# tec_controller.net
KiCad netlist of a schematic drawn in EAGLE
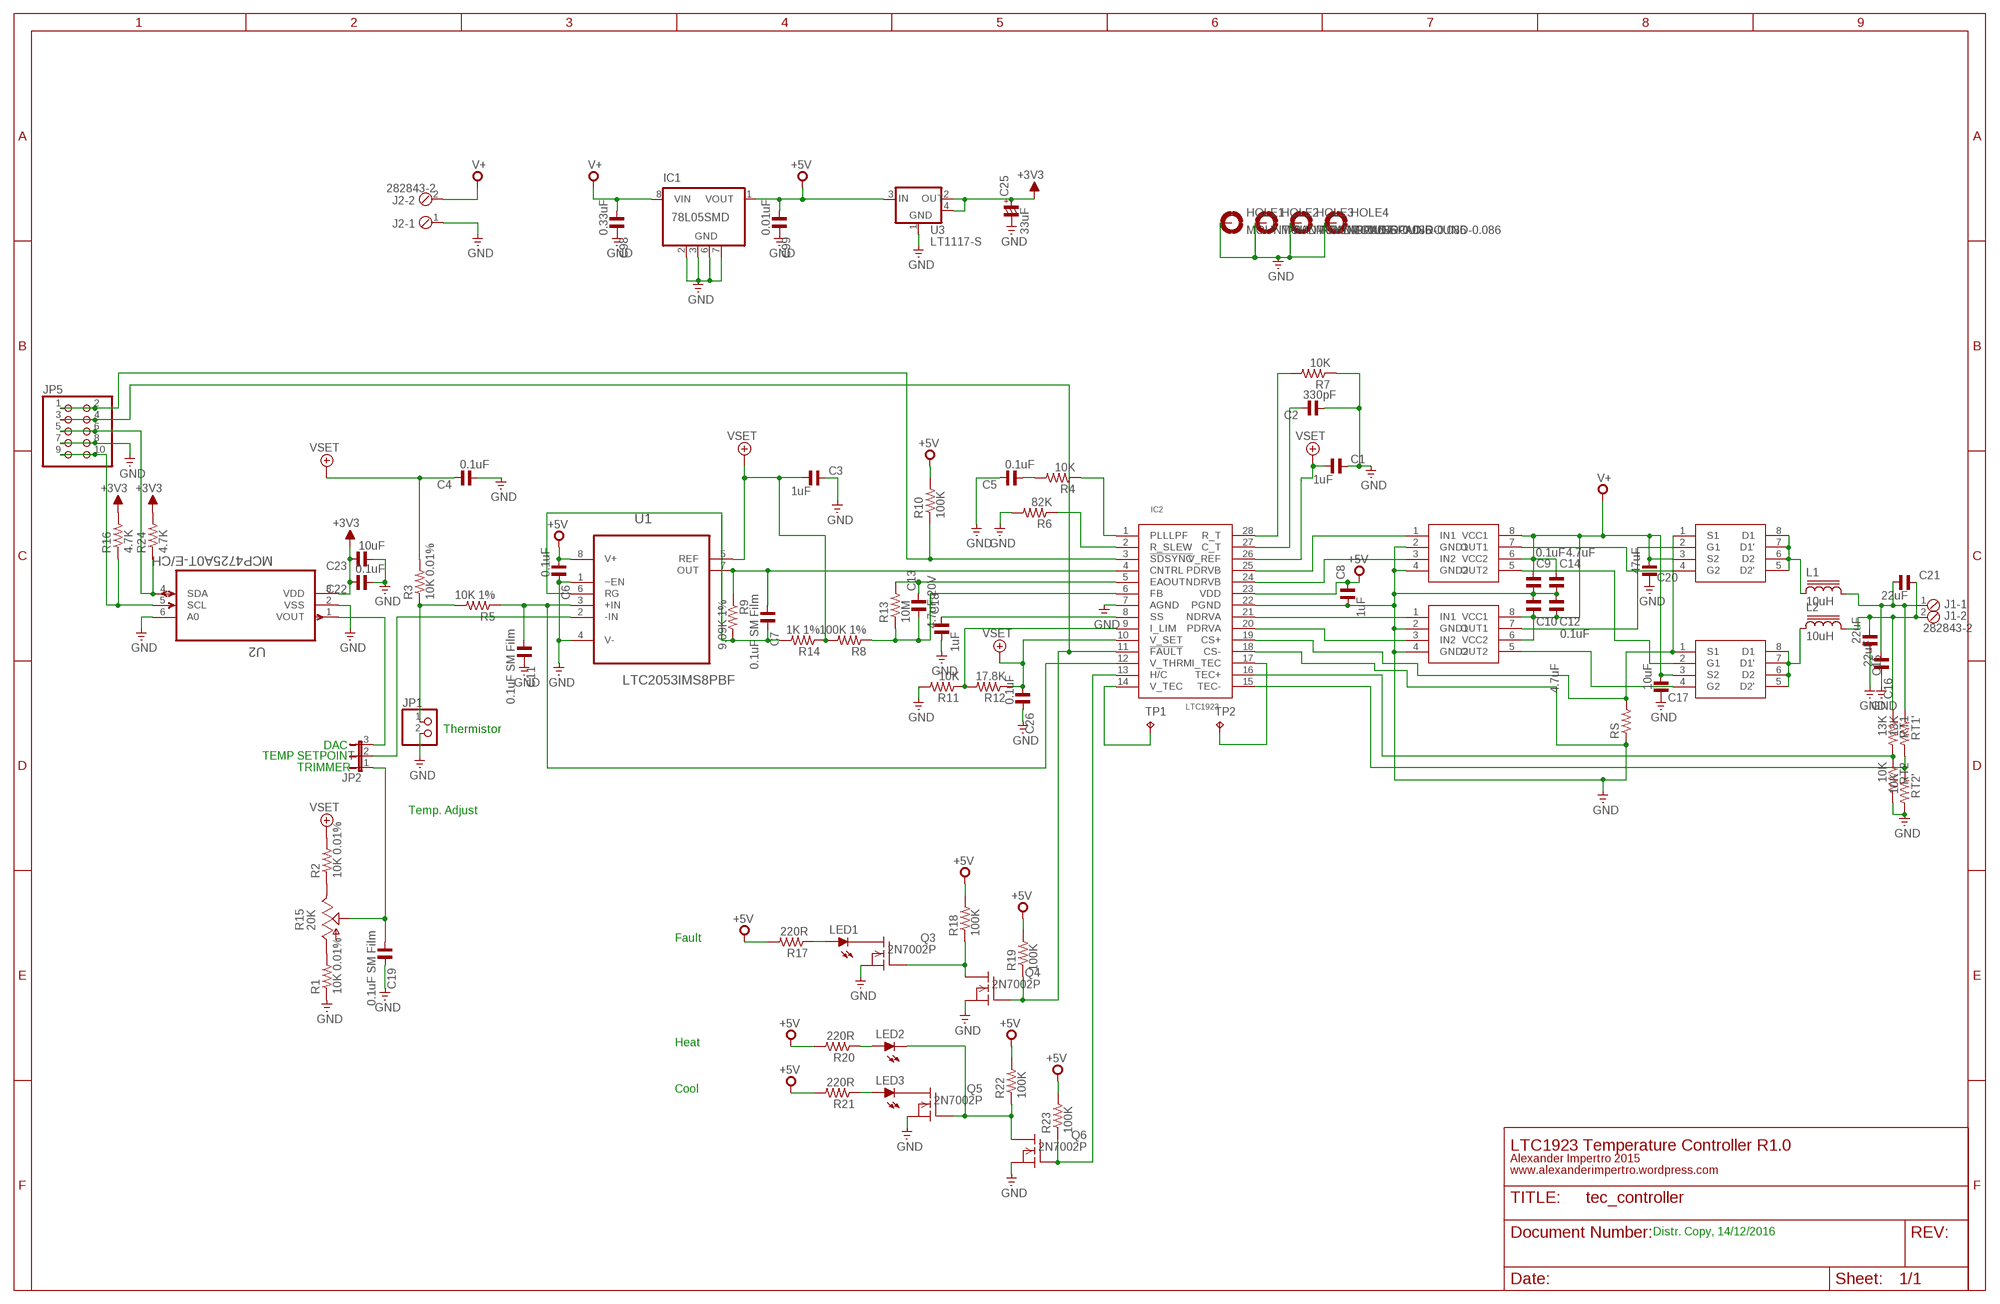
[diagram p0: schematic, sheet 1]

(export (version "E")
  (design (tool "Eeschema 10.0.6"))
  (components
    (comp (ref "C1")
      (value "1uF")
      (footprint "eagle-import:C0603")
      (libsource (lib "eagle-import") (part "C-EUC0603"))
    )
    (comp (ref "C2")
      (value "330pF")
      (footprint "eagle-import:C0603")
      (libsource (lib "eagle-import") (part "C-EUC0603"))
    )
    (comp (ref "C3")
      (value "1uF")
      (footprint "eagle-import:C0603")
      (libsource (lib "eagle-import") (part "C-EUC0603"))
    )
    (comp (ref "C4")
      (value "0.1uF")
      (footprint "eagle-import:C0603")
      (libsource (lib "eagle-import") (part "C-EUC0603"))
    )
    (comp (ref "C5")
      (value "0.1uF")
      (footprint "eagle-import:C0603")
      (libsource (lib "eagle-import") (part "C-EUC0603"))
    )
    (comp (ref "C6")
      (value "0.1uF")
      (footprint "eagle-import:C0603")
      (libsource (lib "eagle-import") (part "C-EUC0603"))
    )
    (comp (ref "C7")
      (value "0.1uF SM Film")
      (footprint "eagle-import:C0805")
      (libsource (lib "eagle-import") (part "C-EUC0805"))
    )
    (comp (ref "C8")
      (value "1uF")
      (footprint "eagle-import:C0603")
      (libsource (lib "eagle-import") (part "C-EUC0603"))
    )
    (comp (ref "C9")
      (value "0.1uF")
      (footprint "eagle-import:C0603")
      (libsource (lib "eagle-import") (part "C-EUC0603"))
    )
    (comp (ref "C10")
      (value "4.7uF")
      (footprint "eagle-import:C0603")
      (libsource (lib "eagle-import") (part "C-EUC0603"))
    )
    (comp (ref "C11")
      (value "0.1uF SM Film")
      (footprint "eagle-import:C0805")
      (libsource (lib "eagle-import") (part "C-EUC0805"))
    )
    (comp (ref "C12")
      (value "0.1uF")
      (footprint "eagle-import:C0603")
      (libsource (lib "eagle-import") (part "C-EUC0603"))
    )
    (comp (ref "C13")
      (value "4.7uF 20V")
      (footprint "eagle-import:C1206")
      (libsource (lib "eagle-import") (part "C-EUC1206"))
    )
    (comp (ref "C14")
      (value "4.7uF")
      (footprint "eagle-import:C0603")
      (libsource (lib "eagle-import") (part "C-EUC0603"))
    )
    (comp (ref "C15")
      (value "22uF")
      (footprint "eagle-import:C0603")
      (libsource (lib "eagle-import") (part "C-EUC0603"))
    )
    (comp (ref "C16")
      (value "22uF")
      (footprint "eagle-import:C0603")
      (libsource (lib "eagle-import") (part "C-EUC0603"))
    )
    (comp (ref "C17")
      (value "10uF")
      (footprint "eagle-import:C0603")
      (libsource (lib "eagle-import") (part "C-EUC0603"))
    )
    (comp (ref "C18")
      (value "1uF")
      (footprint "eagle-import:C0603")
      (libsource (lib "eagle-import") (part "C-EUC0603"))
    )
    (comp (ref "C19")
      (value "0.1uF SM Film")
      (footprint "eagle-import:C0805")
      (libsource (lib "eagle-import") (part "C-EUC0805"))
    )
    (comp (ref "C20")
      (value "47uF")
      (footprint "eagle-import:C0805")
      (libsource (lib "eagle-import") (part "C-EUC0805"))
    )
    (comp (ref "C21")
      (value "22uF")
      (footprint "eagle-import:C0603")
      (libsource (lib "eagle-import") (part "C-EUC0603"))
    )
    (comp (ref "C22")
      (value "0.1uF")
      (footprint "eagle-import:C0603")
      (libsource (lib "eagle-import") (part "C-EUC0603"))
    )
    (comp (ref "C23")
      (value "10uF")
      (footprint "eagle-import:C0603")
      (libsource (lib "eagle-import") (part "C-EUC0603"))
    )
    (comp (ref "C25")
      (value "33uF")
      (footprint "eagle-import:153CLV-0505")
      (libsource (lib "eagle-import") (part "CPOL-EU153CLV-0505"))
    )
    (comp (ref "C26")
      (value "0.1uF")
      (footprint "eagle-import:C0603")
      (libsource (lib "eagle-import") (part "C-EUC0603"))
    )
    (comp (ref "C98")
      (value "0.33uF")
      (footprint "eagle-import:C0805")
      (libsource (lib "eagle-import") (part "C-EUC0805"))
    )
    (comp (ref "C99")
      (value "0.01uF")
      (footprint "eagle-import:C0805")
      (libsource (lib "eagle-import") (part "C-EUC0805"))
    )
    (comp (ref "HOLE1")
      (value "MOUNT-PAD-ROUND-0.086")
      (footprint "eagle-import:086-PAD")
      (libsource (lib "eagle-import") (part "MOUNT-PAD-ROUND-0.086"))
    )
    (comp (ref "HOLE2")
      (value "MOUNT-PAD-ROUND-0.086")
      (footprint "eagle-import:086-PAD")
      (libsource (lib "eagle-import") (part "MOUNT-PAD-ROUND-0.086"))
    )
    (comp (ref "HOLE3")
      (value "MOUNT-PAD-ROUND-0.086")
      (footprint "eagle-import:086-PAD")
      (libsource (lib "eagle-import") (part "MOUNT-PAD-ROUND-0.086"))
    )
    (comp (ref "HOLE4")
      (value "MOUNT-PAD-ROUND-0.086")
      (footprint "eagle-import:086-PAD")
      (libsource (lib "eagle-import") (part "MOUNT-PAD-ROUND-0.086"))
    )
    (comp (ref "IC1")
      (value "78L05SMD")
      (footprint "eagle-import:SO08")
      (libsource (lib "eagle-import") (part "78LSMD05"))
    )
    (comp (ref "IC2")
      (value "LTC1923")
      (footprint "eagle-import:SSOP28")
      (libsource (lib "eagle-import") (part "LTC1923"))
    )
    (comp (ref "IC3")
      (value "LTC1693-1")
      (footprint "eagle-import:SO-08")
      (libsource (lib "eagle-import") (part "LTC1693-1"))
    )
    (comp (ref "IC4")
      (value "LTC1693-1")
      (footprint "eagle-import:SO-08")
      (libsource (lib "eagle-import") (part "LTC1693-1"))
    )
    (comp (ref "IC5")
      (value "IRF7343")
      (footprint "eagle-import:SO-08")
      (libsource (lib "eagle-import") (part "IRF7343"))
    )
    (comp (ref "IC6")
      (value "IRF7343")
      (footprint "eagle-import:SO-08")
      (libsource (lib "eagle-import") (part "IRF7343"))
    )
    (comp (ref "J1")
      (value "282843-2")
      (footprint "eagle-import:282843-2")
      (libsource (lib "eagle-import") (part "282843-2"))
    )
    (comp (ref "J2")
      (value "282843-2")
      (footprint "eagle-import:282843-2")
      (libsource (lib "eagle-import") (part "282843-2"))
    )
    (comp (ref "JP1")
      (value "PINHD-1X2")
      (footprint "eagle-import:1X02")
      (libsource (lib "eagle-import") (part "PINHD-1X2"))
    )
    (comp (ref "JP2")
      (value "JP2E")
      (footprint "eagle-import:JP2")
      (libsource (lib "eagle-import") (part "JP2E"))
    )
    (comp (ref "JP5")
      (value "PINHD-2X5")
      (footprint "eagle-import:2X05")
      (libsource (lib "eagle-import") (part "PINHD-2X5"))
    )
    (comp (ref "L1")
      (value "10uH")
      (footprint "eagle-import:DRA127")
      (libsource (lib "eagle-import") (part "DRA127"))
    )
    (comp (ref "L2")
      (value "10uH")
      (footprint "eagle-import:DRA127")
      (libsource (lib "eagle-import") (part "DRA127"))
    )
    (comp (ref "LED1")
      (value "LEDCHIPLED_0805")
      (footprint "eagle-import:CHIPLED_0805")
      (libsource (lib "eagle-import") (part "LEDCHIPLED_0805"))
    )
    (comp (ref "LED2")
      (value "LEDCHIPLED_0805")
      (footprint "eagle-import:CHIPLED_0805")
      (libsource (lib "eagle-import") (part "LEDCHIPLED_0805"))
    )
    (comp (ref "LED3")
      (value "LEDCHIPLED_0805")
      (footprint "eagle-import:CHIPLED_0805")
      (libsource (lib "eagle-import") (part "LEDCHIPLED_0805"))
    )
    (comp (ref "Q3")
      (value "2N7002P")
      (footprint "eagle-import:SOT95P230X110-3N")
      (libsource (lib "eagle-import") (part "2N7002P"))
    )
    (comp (ref "Q4")
      (value "2N7002P")
      (footprint "eagle-import:SOT95P230X110-3N")
      (libsource (lib "eagle-import") (part "2N7002P"))
    )
    (comp (ref "Q5")
      (value "2N7002P")
      (footprint "eagle-import:SOT95P230X110-3N")
      (libsource (lib "eagle-import") (part "2N7002P"))
    )
    (comp (ref "Q6")
      (value "2N7002P")
      (footprint "eagle-import:SOT95P230X110-3N")
      (libsource (lib "eagle-import") (part "2N7002P"))
    )
    (comp (ref "R1")
      (value "10K 0.01%")
      (footprint "eagle-import:R0603")
      (libsource (lib "eagle-import") (part "R-EU_R0603"))
    )
    (comp (ref "R2")
      (value "10K 0.01%")
      (footprint "eagle-import:R0603")
      (libsource (lib "eagle-import") (part "R-EU_R0603"))
    )
    (comp (ref "R3")
      (value "10K 0.01%")
      (footprint "eagle-import:R0603")
      (libsource (lib "eagle-import") (part "R-EU_R0603"))
    )
    (comp (ref "R4")
      (value "10K")
      (footprint "eagle-import:R0603")
      (libsource (lib "eagle-import") (part "R-EU_R0603"))
    )
    (comp (ref "R5")
      (value "10K 1%")
      (footprint "eagle-import:R0603")
      (libsource (lib "eagle-import") (part "R-EU_R0603"))
    )
    (comp (ref "R6")
      (value "82K")
      (footprint "eagle-import:R0603")
      (libsource (lib "eagle-import") (part "R-EU_R0603"))
    )
    (comp (ref "R7")
      (value "10K")
      (footprint "eagle-import:R0603")
      (libsource (lib "eagle-import") (part "R-EU_R0603"))
    )
    (comp (ref "R8")
      (value "100K 1%")
      (footprint "eagle-import:R0603")
      (libsource (lib "eagle-import") (part "R-EU_R0603"))
    )
    (comp (ref "R9")
      (value "9.09K 1%")
      (footprint "eagle-import:R0603")
      (libsource (lib "eagle-import") (part "R-EU_R0603"))
    )
    (comp (ref "R10")
      (value "100K")
      (footprint "eagle-import:R0805")
      (libsource (lib "eagle-import") (part "R-EU_R0805"))
    )
    (comp (ref "R11")
      (value "10K")
      (footprint "eagle-import:R0603")
      (libsource (lib "eagle-import") (part "R-EU_R0603"))
    )
    (comp (ref "R12")
      (value "17.8K")
      (footprint "eagle-import:R0805")
      (libsource (lib "eagle-import") (part "R-EU_R0805"))
    )
    (comp (ref "R13")
      (value "10M")
      (footprint "eagle-import:R0805")
      (libsource (lib "eagle-import") (part "R-EU_R0805"))
    )
    (comp (ref "R14")
      (value "1K 1%")
      (footprint "eagle-import:R0603")
      (libsource (lib "eagle-import") (part "R-EU_R0603"))
    )
    (comp (ref "R15")
      (value "20K")
      (footprint "eagle-import:B25P")
      (libsource (lib "eagle-import") (part "TRIM_US-B25P"))
    )
    (comp (ref "R16")
      (value "4.7K")
      (footprint "eagle-import:R0603")
      (libsource (lib "eagle-import") (part "R-EU_R0603"))
    )
    (comp (ref "R17")
      (value "220R")
      (footprint "eagle-import:R0603")
      (libsource (lib "eagle-import") (part "R-EU_R0603"))
    )
    (comp (ref "R18")
      (value "100K")
      (footprint "eagle-import:R0603")
      (libsource (lib "eagle-import") (part "R-EU_R0603"))
    )
    (comp (ref "R19")
      (value "100K")
      (footprint "eagle-import:R0603")
      (libsource (lib "eagle-import") (part "R-EU_R0603"))
    )
    (comp (ref "R20")
      (value "220R")
      (footprint "eagle-import:R0603")
      (libsource (lib "eagle-import") (part "R-EU_R0603"))
    )
    (comp (ref "R21")
      (value "220R")
      (footprint "eagle-import:R0603")
      (libsource (lib "eagle-import") (part "R-EU_R0603"))
    )
    (comp (ref "R22")
      (value "100K")
      (footprint "eagle-import:R0603")
      (libsource (lib "eagle-import") (part "R-EU_R0603"))
    )
    (comp (ref "R23")
      (value "100K")
      (footprint "eagle-import:R0603")
      (libsource (lib "eagle-import") (part "R-EU_R0603"))
    )
    (comp (ref "R24")
      (value "4.7K")
      (footprint "eagle-import:R0603")
      (libsource (lib "eagle-import") (part "R-EU_R0603"))
    )
    (comp (ref "RS")
      (value "R-EU_R2512")
      (footprint "eagle-import:R2512")
      (libsource (lib "eagle-import") (part "R-EU_R2512"))
    )
    (comp (ref "RT1")
      (value "13K")
      (footprint "eagle-import:R0603")
      (libsource (lib "eagle-import") (part "R-EU_R0603"))
    )
    (comp (ref "RT1'")
      (value "13K")
      (footprint "eagle-import:R0603")
      (libsource (lib "eagle-import") (part "R-EU_R0603"))
    )
    (comp (ref "RT2")
      (value "10K")
      (footprint "eagle-import:R0603")
      (libsource (lib "eagle-import") (part "R-EU_R0603"))
    )
    (comp (ref "RT2'")
      (value "10K")
      (footprint "eagle-import:R0603")
      (libsource (lib "eagle-import") (part "R-EU_R0603"))
    )
    (comp (ref "TP1")
      (value "TPTP10SQ")
      (footprint "eagle-import:TP10SQ")
      (libsource (lib "eagle-import") (part "TPTP10SQ"))
    )
    (comp (ref "TP2")
      (value "TPTP10SQ")
      (footprint "eagle-import:TP10SQ")
      (libsource (lib "eagle-import") (part "TPTP10SQ"))
    )
    (comp (ref "U1")
      (value "LTC2053IMS8PBF")
      (footprint "eagle-import:SOP65P490X110-8N")
      (fields (field (name "MPN") "LTC2053IMS8#PBF"))
      (libsource (lib "eagle-import") (part "LTC2053IMS8PBF"))
    )
    (comp (ref "U2")
      (value "MCP4725A0T-E/CH")
      (footprint "eagle-import:SOT95P270X145-6N")
      (libsource (lib "eagle-import") (part "MCP4725A0T-E/CH"))
    )
    (comp (ref "U3")
      (value "LT1117-S")
      (footprint "eagle-import:SOT223")
      (libsource (lib "eagle-import") (part "LT1117-S"))
    )
  )
  (nets
    (net (code "1") (name "+3V3") (class "Default")
      (node (ref "C22") (pin "1") (pinfunction "1_1") (pintype "passive"))
      (node (ref "C23") (pin "1") (pinfunction "1_1") (pintype "passive"))
      (node (ref "C25") (pin "+") (pinfunction "+_+") (pintype "passive"))
      (node (ref "R16") (pin "2") (pinfunction "2_2") (pintype "passive"))
      (node (ref "R24") (pin "2") (pinfunction "2_2") (pintype "passive"))
      (node (ref "U2") (pin "3") (pinfunction "VDD_3") (pintype "power_in"))
      (node (ref "U3") (pin "2") (pinfunction "OUT_2") (pintype "passive"))
      (node (ref "U3") (pin "4") (pinfunction "TAB_4") (pintype "passive"))
    )
    (net (code "2") (name "+5V") (class "Default")
      (node (ref "C6") (pin "2") (pinfunction "2_2") (pintype "passive"))
      (node (ref "C8") (pin "1") (pinfunction "1_1") (pintype "passive"))
      (node (ref "C99") (pin "2") (pinfunction "2_2") (pintype "passive"))
      (node (ref "IC1") (pin "1") (pinfunction "VOUT_1") (pintype "output"))
      (node (ref "IC2") (pin "23") (pinfunction "VDD_23") (pintype "bidirectional"))
      (node (ref "R10") (pin "2") (pinfunction "2_2") (pintype "passive"))
      (node (ref "R17") (pin "2") (pinfunction "2_2") (pintype "passive"))
      (node (ref "R18") (pin "2") (pinfunction "2_2") (pintype "passive"))
      (node (ref "R19") (pin "2") (pinfunction "2_2") (pintype "passive"))
      (node (ref "R20") (pin "2") (pinfunction "2_2") (pintype "passive"))
      (node (ref "R21") (pin "2") (pinfunction "2_2") (pintype "passive"))
      (node (ref "R22") (pin "2") (pinfunction "2_2") (pintype "passive"))
      (node (ref "R23") (pin "2") (pinfunction "2_2") (pintype "passive"))
      (node (ref "U1") (pin "8") (pinfunction "V+_8") (pintype "power_in"))
      (node (ref "U3") (pin "3") (pinfunction "IN_3") (pintype "input"))
    )
    (net (code "3") (name "GND") (class "Default")
      (node (ref "C1") (pin "1") (pinfunction "1_1") (pintype "passive"))
      (node (ref "C10") (pin "2") (pinfunction "2_2") (pintype "passive"))
      (node (ref "C11") (pin "1") (pinfunction "1_1") (pintype "passive"))
      (node (ref "C12") (pin "2") (pinfunction "2_2") (pintype "passive"))
      (node (ref "C14") (pin "1") (pinfunction "1_1") (pintype "passive"))
      (node (ref "C15") (pin "1") (pinfunction "1_1") (pintype "passive"))
      (node (ref "C16") (pin "1") (pinfunction "1_1") (pintype "passive"))
      (node (ref "C17") (pin "1") (pinfunction "1_1") (pintype "passive"))
      (node (ref "C18") (pin "2") (pinfunction "2_2") (pintype "passive"))
      (node (ref "C19") (pin "1") (pinfunction "1_1") (pintype "passive"))
      (node (ref "C2") (pin "2") (pinfunction "2_2") (pintype "passive"))
      (node (ref "C20") (pin "1") (pinfunction "1_1") (pintype "passive"))
      (node (ref "C22") (pin "2") (pinfunction "2_2") (pintype "passive"))
      (node (ref "C23") (pin "2") (pinfunction "2_2") (pintype "passive"))
      (node (ref "C25") (pin "-") (pinfunction "-_-") (pintype "passive"))
      (node (ref "C26") (pin "1") (pinfunction "1_1") (pintype "passive"))
      (node (ref "C3") (pin "1") (pinfunction "1_1") (pintype "passive"))
      (node (ref "C4") (pin "2") (pinfunction "2_2") (pintype "passive"))
      (node (ref "C5") (pin "1") (pinfunction "1_1") (pintype "passive"))
      (node (ref "C6") (pin "1") (pinfunction "1_1") (pintype "passive"))
      (node (ref "C8") (pin "2") (pinfunction "2_2") (pintype "passive"))
      (node (ref "C9") (pin "1") (pinfunction "1_1") (pintype "passive"))
      (node (ref "C98") (pin "1") (pinfunction "1_1") (pintype "passive"))
      (node (ref "C99") (pin "1") (pinfunction "1_1") (pintype "passive"))
      (node (ref "HOLE1") (pin "B086") (pinfunction "MOUNT_B086") (pintype "passive"))
      (node (ref "HOLE2") (pin "B086") (pinfunction "MOUNT_B086") (pintype "passive"))
      (node (ref "HOLE3") (pin "B086") (pinfunction "MOUNT_B086") (pintype "passive"))
      (node (ref "HOLE4") (pin "B086") (pinfunction "MOUNT_B086") (pintype "passive"))
      (node (ref "IC1") (pin "2") (pinfunction "GND_2") (pintype "power_in"))
      (node (ref "IC1") (pin "3") (pinfunction "GND_3") (pintype "power_in"))
      (node (ref "IC1") (pin "6") (pinfunction "GND_6") (pintype "power_in"))
      (node (ref "IC1") (pin "7") (pinfunction "GND_7") (pintype "power_in"))
      (node (ref "IC2") (pin "18") (pinfunction "CS-_18") (pintype "bidirectional"))
      (node (ref "IC2") (pin "22") (pinfunction "PGND_22") (pintype "bidirectional"))
      (node (ref "IC2") (pin "7") (pinfunction "AGND_7") (pintype "bidirectional"))
      (node (ref "IC3") (pin "2") (pinfunction "GND1_2") (pintype "bidirectional"))
      (node (ref "IC3") (pin "4") (pinfunction "GND2_4") (pintype "bidirectional"))
      (node (ref "IC4") (pin "2") (pinfunction "GND1_2") (pintype "bidirectional"))
      (node (ref "IC4") (pin "4") (pinfunction "GND2_4") (pintype "bidirectional"))
      (node (ref "J2") (pin "1") (pinfunction "1_1") (pintype "passive"))
      (node (ref "JP1") (pin "2") (pinfunction "2_2") (pintype "passive"))
      (node (ref "JP5") (pin "7") (pinfunction "7_7") (pintype "passive"))
      (node (ref "JP5") (pin "8") (pinfunction "8_8") (pintype "passive"))
      (node (ref "Q3") (pin "2") (pinfunction "S_2") (pintype "passive"))
      (node (ref "Q4") (pin "2") (pinfunction "S_2") (pintype "passive"))
      (node (ref "Q5") (pin "2") (pinfunction "S_2") (pintype "passive"))
      (node (ref "Q6") (pin "2") (pinfunction "S_2") (pintype "passive"))
      (node (ref "R1") (pin "1") (pinfunction "1_1") (pintype "passive"))
      (node (ref "R11") (pin "2") (pinfunction "2_2") (pintype "passive"))
      (node (ref "R6") (pin "2") (pinfunction "2_2") (pintype "passive"))
      (node (ref "R7") (pin "1") (pinfunction "1_1") (pintype "passive"))
      (node (ref "RS") (pin "1") (pinfunction "1_1") (pintype "passive"))
      (node (ref "RT2") (pin "2") (pinfunction "2_2") (pintype "passive"))
      (node (ref "RT2'") (pin "2") (pinfunction "2_2") (pintype "passive"))
      (node (ref "U1") (pin "1") (pinfunction "~{EN}_1") (pintype "input"))
      (node (ref "U1") (pin "4") (pinfunction "V-_4") (pintype "power_in"))
      (node (ref "U2") (pin "2") (pinfunction "VSS_2") (pintype "power_in"))
      (node (ref "U2") (pin "6") (pinfunction "A0_6") (pintype "passive"))
      (node (ref "U3") (pin "1") (pinfunction "GND_1") (pintype "input"))
    )
    (net (code "4") (name "Net-(C5-Pad2)") (class "Default")
      (node (ref "C5") (pin "2") (pinfunction "2_2") (pintype "passive"))
      (node (ref "R4") (pin "2") (pinfunction "2_2") (pintype "passive"))
    )
    (net (code "5") (name "Net-(C16-Pad2)") (class "Default")
      (node (ref "C16") (pin "2") (pinfunction "2_2") (pintype "passive"))
      (node (ref "C21") (pin "2") (pinfunction "2_2") (pintype "passive"))
      (node (ref "J1") (pin "1") (pinfunction "1_1") (pintype "passive"))
      (node (ref "L1") (pin "2") (pinfunction "2_2") (pintype "passive"))
      (node (ref "RT1'") (pin "1") (pinfunction "1_1") (pintype "passive"))
    )
    (net (code "6") (name "Net-(C19-Pad2)") (class "Default")
      (node (ref "C19") (pin "2") (pinfunction "2_2") (pintype "passive"))
      (node (ref "JP2") (pin "1") (pinfunction "1_1") (pintype "passive"))
      (node (ref "R15") (pin "S") (pinfunction "S_S") (pintype "passive"))
    )
    (net (code "7") (name "Net-(IC2-CNTRL)") (class "Default")
      (node (ref "C7") (pin "2") (pinfunction "2_2") (pintype "passive"))
      (node (ref "IC2") (pin "4") (pinfunction "CNTRL_4") (pintype "bidirectional"))
      (node (ref "R9") (pin "1") (pinfunction "1_1") (pintype "passive"))
      (node (ref "U1") (pin "7") (pinfunction "OUT_7") (pintype "output"))
    )
    (net (code "8") (name "Net-(IC2-CS+)") (class "Default")
      (node (ref "IC2") (pin "19") (pinfunction "CS+_19") (pintype "bidirectional"))
      (node (ref "IC5") (pin "1") (pinfunction "S1_1") (pintype "bidirectional"))
      (node (ref "IC6") (pin "1") (pinfunction "S1_1") (pintype "bidirectional"))
      (node (ref "RS") (pin "2") (pinfunction "2_2") (pintype "passive"))
    )
    (net (code "9") (name "Net-(IC2-C_T)") (class "Default")
      (node (ref "C2") (pin "1") (pinfunction "1_1") (pintype "passive"))
      (node (ref "IC2") (pin "27") (pinfunction "C_T_27") (pintype "bidirectional"))
    )
    (net (code "10") (name "Net-(IC2-EAOUT)") (class "Default")
      (node (ref "C13") (pin "1") (pinfunction "1_1") (pintype "passive"))
      (node (ref "IC2") (pin "5") (pinfunction "EAOUT_5") (pintype "bidirectional"))
      (node (ref "R13") (pin "2") (pinfunction "2_2") (pintype "passive"))
    )
    (net (code "11") (name "Net-(IC2-FB)") (class "Default")
      (node (ref "C13") (pin "2") (pinfunction "2_2") (pintype "passive"))
      (node (ref "IC2") (pin "6") (pinfunction "FB_6") (pintype "bidirectional"))
      (node (ref "R13") (pin "1") (pinfunction "1_1") (pintype "passive"))
      (node (ref "R8") (pin "1") (pinfunction "1_1") (pintype "passive"))
    )
    (net (code "12") (name "Net-(IC2-H{slash}C)") (class "Default")
      (node (ref "IC2") (pin "13") (pinfunction "H/C_13") (pintype "bidirectional"))
      (node (ref "Q6") (pin "1") (pinfunction "G_1") (pintype "passive"))
      (node (ref "R23") (pin "1") (pinfunction "1_1") (pintype "passive"))
    )
    (net (code "13") (name "Net-(IC2-I_LIM)") (class "Default")
      (node (ref "IC2") (pin "9") (pinfunction "I_LIM_9") (pintype "bidirectional"))
      (node (ref "R11") (pin "1") (pinfunction "1_1") (pintype "passive"))
      (node (ref "R12") (pin "2") (pinfunction "2_2") (pintype "passive"))
    )
    (net (code "14") (name "Net-(IC2-I_TEC)") (class "Default")
      (node (ref "IC2") (pin "17") (pinfunction "I_TEC_17") (pintype "bidirectional"))
      (node (ref "TP2") (pin "TP") (pinfunction "TP_TP") (pintype "input"))
    )
    (net (code "15") (name "Net-(IC2-NDRVA)") (class "Default")
      (node (ref "IC2") (pin "21") (pinfunction "NDRVA_21") (pintype "bidirectional"))
      (node (ref "IC4") (pin "1") (pinfunction "IN1_1") (pintype "bidirectional"))
    )
    (net (code "16") (name "Net-(IC2-NDRVB)") (class "Default")
      (node (ref "IC2") (pin "24") (pinfunction "NDRVB_24") (pintype "bidirectional"))
      (node (ref "IC3") (pin "3") (pinfunction "IN2_3") (pintype "bidirectional"))
    )
    (net (code "17") (name "Net-(IC2-PDRVA)") (class "Default")
      (node (ref "IC2") (pin "20") (pinfunction "PDRVA_20") (pintype "bidirectional"))
      (node (ref "IC4") (pin "3") (pinfunction "IN2_3") (pintype "bidirectional"))
    )
    (net (code "18") (name "Net-(IC2-PDRVB)") (class "Default")
      (node (ref "IC2") (pin "25") (pinfunction "PDRVB_25") (pintype "bidirectional"))
      (node (ref "IC3") (pin "1") (pinfunction "IN1_1") (pintype "bidirectional"))
    )
    (net (code "19") (name "Net-(IC2-PLLLPF)") (class "Default")
      (node (ref "IC2") (pin "1") (pinfunction "PLLLPF_1") (pintype "bidirectional"))
      (node (ref "R4") (pin "1") (pinfunction "1_1") (pintype "passive"))
    )
    (net (code "20") (name "Net-(IC2-R_SLEW)") (class "Default")
      (node (ref "IC2") (pin "2") (pinfunction "R_SLEW_2") (pintype "bidirectional"))
      (node (ref "R6") (pin "1") (pinfunction "1_1") (pintype "passive"))
    )
    (net (code "21") (name "Net-(IC2-R_T)") (class "Default")
      (node (ref "IC2") (pin "28") (pinfunction "R_T_28") (pintype "bidirectional"))
      (node (ref "R7") (pin "2") (pinfunction "2_2") (pintype "passive"))
    )
    (net (code "22") (name "Net-(IC2-SS)") (class "Default")
      (node (ref "C18") (pin "1") (pinfunction "1_1") (pintype "passive"))
      (node (ref "IC2") (pin "8") (pinfunction "SS_8") (pintype "bidirectional"))
    )
    (net (code "23") (name "Net-(IC2-TEC+)") (class "Default")
      (node (ref "IC2") (pin "16") (pinfunction "TEC+_16") (pintype "bidirectional"))
      (node (ref "RT1") (pin "2") (pinfunction "2_2") (pintype "passive"))
      (node (ref "RT2") (pin "1") (pinfunction "1_1") (pintype "passive"))
    )
    (net (code "24") (name "Net-(IC2-TEC-)") (class "Default")
      (node (ref "IC2") (pin "15") (pinfunction "TEC-_15") (pintype "bidirectional"))
      (node (ref "RT1'") (pin "2") (pinfunction "2_2") (pintype "passive"))
      (node (ref "RT2'") (pin "1") (pinfunction "1_1") (pintype "passive"))
    )
    (net (code "25") (name "Net-(IC2-V_TEC)") (class "Default")
      (node (ref "IC2") (pin "14") (pinfunction "V_TEC_14") (pintype "bidirectional"))
      (node (ref "TP1") (pin "TP") (pinfunction "TP_TP") (pintype "input"))
    )
    (net (code "26") (name "Net-(IC2-V_THRM)") (class "Default")
      (node (ref "C11") (pin "2") (pinfunction "2_2") (pintype "passive"))
      (node (ref "IC2") (pin "12") (pinfunction "V_THRM_12") (pintype "bidirectional"))
      (node (ref "R5") (pin "1") (pinfunction "1_1") (pintype "passive"))
      (node (ref "U1") (pin "3") (pinfunction "+IN_3") (pintype "input"))
    )
    (net (code "27") (name "Net-(IC2-~{FAULT})") (class "Default")
      (node (ref "IC2") (pin "11") (pinfunction "~{FAULT}_11") (pintype "bidirectional"))
      (node (ref "JP5") (pin "3") (pinfunction "3_3") (pintype "passive"))
      (node (ref "JP5") (pin "4") (pinfunction "4_4") (pintype "passive"))
      (node (ref "Q4") (pin "1") (pinfunction "G_1") (pintype "passive"))
      (node (ref "R19") (pin "1") (pinfunction "1_1") (pintype "passive"))
    )
    (net (code "28") (name "Net-(IC2-~{SDSYNC})") (class "Default")
      (node (ref "IC2") (pin "3") (pinfunction "~{SDSYNC}_3") (pintype "bidirectional"))
      (node (ref "JP5") (pin "1") (pinfunction "1_1") (pintype "passive"))
      (node (ref "JP5") (pin "2") (pinfunction "2_2") (pintype "passive"))
      (node (ref "R10") (pin "1") (pinfunction "1_1") (pintype "passive"))
    )
    (net (code "29") (name "Net-(IC3-OUT1)") (class "Default")
      (node (ref "IC3") (pin "7") (pinfunction "OUT1_7") (pintype "bidirectional"))
      (node (ref "IC5") (pin "4") (pinfunction "G2_4") (pintype "bidirectional"))
    )
    (net (code "30") (name "Net-(IC3-OUT2)") (class "Default")
      (node (ref "IC3") (pin "5") (pinfunction "OUT2_5") (pintype "bidirectional"))
      (node (ref "IC6") (pin "2") (pinfunction "G1_2") (pintype "bidirectional"))
    )
    (net (code "31") (name "Net-(IC4-OUT1)") (class "Default")
      (node (ref "IC4") (pin "7") (pinfunction "OUT1_7") (pintype "bidirectional"))
      (node (ref "IC5") (pin "2") (pinfunction "G1_2") (pintype "bidirectional"))
    )
    (net (code "32") (name "Net-(IC4-OUT2)") (class "Default")
      (node (ref "IC4") (pin "5") (pinfunction "OUT2_5") (pintype "bidirectional"))
      (node (ref "IC6") (pin "4") (pinfunction "G2_4") (pintype "bidirectional"))
    )
    (net (code "33") (name "Net-(IC5-D1')") (class "Default")
      (node (ref "IC5") (pin "5") (pinfunction "D2'_5") (pintype "bidirectional"))
      (node (ref "IC5") (pin "6") (pinfunction "D2_6") (pintype "bidirectional"))
      (node (ref "IC5") (pin "7") (pinfunction "D1'_7") (pintype "bidirectional"))
      (node (ref "IC5") (pin "8") (pinfunction "D1_8") (pintype "bidirectional"))
      (node (ref "L1") (pin "1") (pinfunction "1_1") (pintype "passive"))
    )
    (net (code "34") (name "Net-(IC6-D1')") (class "Default")
      (node (ref "IC6") (pin "5") (pinfunction "D2'_5") (pintype "bidirectional"))
      (node (ref "IC6") (pin "6") (pinfunction "D2_6") (pintype "bidirectional"))
      (node (ref "IC6") (pin "7") (pinfunction "D1'_7") (pintype "bidirectional"))
      (node (ref "IC6") (pin "8") (pinfunction "D1_8") (pintype "bidirectional"))
      (node (ref "L2") (pin "1") (pinfunction "1_1") (pintype "passive"))
    )
    (net (code "35") (name "Net-(J1B-1)") (class "Default")
      (node (ref "C15") (pin "2") (pinfunction "2_2") (pintype "passive"))
      (node (ref "C21") (pin "1") (pinfunction "1_1") (pintype "passive"))
      (node (ref "J1") (pin "2") (pinfunction "1_2") (pintype "passive"))
      (node (ref "L2") (pin "2") (pinfunction "2_2") (pintype "passive"))
      (node (ref "RT1") (pin "1") (pinfunction "1_1") (pintype "passive"))
    )
    (net (code "36") (name "Net-(JP1-Pad1)") (class "Default")
      (node (ref "JP1") (pin "1") (pinfunction "1_1") (pintype "passive"))
      (node (ref "R3") (pin "1") (pinfunction "1_1") (pintype "passive"))
      (node (ref "R5") (pin "2") (pinfunction "2_2") (pintype "passive"))
    )
    (net (code "37") (name "Net-(LED1-PadA)") (class "Default")
      (node (ref "LED1") (pin "A") (pinfunction "A_A") (pintype "passive"))
      (node (ref "R17") (pin "1") (pinfunction "1_1") (pintype "passive"))
    )
    (net (code "38") (name "Net-(LED2-PadA)") (class "Default")
      (node (ref "LED2") (pin "A") (pinfunction "A_A") (pintype "passive"))
      (node (ref "R20") (pin "1") (pinfunction "1_1") (pintype "passive"))
    )
    (net (code "39") (name "Net-(LED3-PadA)") (class "Default")
      (node (ref "LED3") (pin "A") (pinfunction "A_A") (pintype "passive"))
      (node (ref "R21") (pin "1") (pinfunction "1_1") (pintype "passive"))
    )
    (net (code "40") (name "Net-(Q3-D)") (class "Default")
      (node (ref "LED1") (pin "C") (pinfunction "C_C") (pintype "passive"))
      (node (ref "Q3") (pin "3") (pinfunction "D_3") (pintype "passive"))
    )
    (net (code "41") (name "Net-(Q3-G)") (class "Default")
      (node (ref "Q3") (pin "1") (pinfunction "G_1") (pintype "passive"))
      (node (ref "Q4") (pin "3") (pinfunction "D_3") (pintype "passive"))
      (node (ref "R18") (pin "1") (pinfunction "1_1") (pintype "passive"))
    )
    (net (code "42") (name "Net-(Q5-D)") (class "Default")
      (node (ref "LED3") (pin "C") (pinfunction "C_C") (pintype "passive"))
      (node (ref "Q5") (pin "3") (pinfunction "D_3") (pintype "passive"))
    )
    (net (code "43") (name "Net-(Q5-G)") (class "Default")
      (node (ref "LED2") (pin "C") (pinfunction "C_C") (pintype "passive"))
      (node (ref "Q5") (pin "1") (pinfunction "G_1") (pintype "passive"))
      (node (ref "Q6") (pin "3") (pinfunction "D_3") (pintype "passive"))
      (node (ref "R22") (pin "1") (pinfunction "1_1") (pintype "passive"))
    )
    (net (code "44") (name "Net-(R1-Pad2)") (class "Default")
      (node (ref "R1") (pin "2") (pinfunction "2_2") (pintype "passive"))
      (node (ref "R15") (pin "A") (pinfunction "A_A") (pintype "passive"))
    )
    (net (code "45") (name "Net-(R15-PadE)") (class "Default")
      (node (ref "R15") (pin "E") (pinfunction "E_E") (pintype "passive"))
      (node (ref "R2") (pin "1") (pinfunction "1_1") (pintype "passive"))
    )
    (net (code "46") (name "Net-(U1--IN)") (class "Default")
      (node (ref "JP2") (pin "2") (pinfunction "2_2") (pintype "passive"))
      (node (ref "U1") (pin "2") (pinfunction "-IN_2") (pintype "input"))
    )
    (net (code "47") (name "Net-(U1-RG)") (class "Default")
      (node (ref "C7") (pin "1") (pinfunction "1_1") (pintype "passive"))
      (node (ref "R14") (pin "2") (pinfunction "2_2") (pintype "passive"))
      (node (ref "R9") (pin "2") (pinfunction "2_2") (pintype "passive"))
      (node (ref "U1") (pin "6") (pinfunction "RG_6") (pintype "input"))
    )
    (net (code "48") (name "Net-(U2-SCL)") (class "Default")
      (node (ref "JP5") (pin "10") (pinfunction "10_10") (pintype "passive"))
      (node (ref "JP5") (pin "9") (pinfunction "9_9") (pintype "passive"))
      (node (ref "R16") (pin "1") (pinfunction "1_1") (pintype "passive"))
      (node (ref "U2") (pin "5") (pinfunction "SCL_5") (pintype "input"))
    )
    (net (code "49") (name "Net-(U2-SDA)") (class "Default")
      (node (ref "JP5") (pin "5") (pinfunction "5_5") (pintype "passive"))
      (node (ref "JP5") (pin "6") (pinfunction "6_6") (pintype "passive"))
      (node (ref "R24") (pin "1") (pinfunction "1_1") (pintype "passive"))
      (node (ref "U2") (pin "4") (pinfunction "SDA_4") (pintype "bidirectional"))
    )
    (net (code "50") (name "Net-(U2-VOUT)") (class "Default")
      (node (ref "JP2") (pin "3") (pinfunction "3_3") (pintype "passive"))
      (node (ref "U2") (pin "1") (pinfunction "VOUT_1") (pintype "output"))
    )
    (net (code "51") (name "V+") (class "Default")
      (node (ref "C10") (pin "1") (pinfunction "1_1") (pintype "passive"))
      (node (ref "C12") (pin "1") (pinfunction "1_1") (pintype "passive"))
      (node (ref "C14") (pin "2") (pinfunction "2_2") (pintype "passive"))
      (node (ref "C17") (pin "2") (pinfunction "2_2") (pintype "passive"))
      (node (ref "C20") (pin "2") (pinfunction "2_2") (pintype "passive"))
      (node (ref "C9") (pin "2") (pinfunction "2_2") (pintype "passive"))
      (node (ref "C98") (pin "2") (pinfunction "2_2") (pintype "passive"))
      (node (ref "IC1") (pin "8") (pinfunction "VIN_8") (pintype "passive"))
      (node (ref "IC3") (pin "6") (pinfunction "VCC2_6") (pintype "bidirectional"))
      (node (ref "IC3") (pin "8") (pinfunction "VCC1_8") (pintype "bidirectional"))
      (node (ref "IC4") (pin "6") (pinfunction "VCC2_6") (pintype "bidirectional"))
      (node (ref "IC4") (pin "8") (pinfunction "VCC1_8") (pintype "bidirectional"))
      (node (ref "IC5") (pin "3") (pinfunction "S2_3") (pintype "bidirectional"))
      (node (ref "IC6") (pin "3") (pinfunction "S2_3") (pintype "bidirectional"))
      (node (ref "J2") (pin "2") (pinfunction "1_2") (pintype "passive"))
    )
    (net (code "52") (name "VSET") (class "Default")
      (node (ref "C1") (pin "2") (pinfunction "2_2") (pintype "passive"))
      (node (ref "C26") (pin "2") (pinfunction "2_2") (pintype "passive"))
      (node (ref "C3") (pin "2") (pinfunction "2_2") (pintype "passive"))
      (node (ref "C4") (pin "1") (pinfunction "1_1") (pintype "passive"))
      (node (ref "IC2") (pin "10") (pinfunction "V_SET_10") (pintype "bidirectional"))
      (node (ref "IC2") (pin "26") (pinfunction "V_REF_26") (pintype "bidirectional"))
      (node (ref "R12") (pin "1") (pinfunction "1_1") (pintype "passive"))
      (node (ref "R14") (pin "1") (pinfunction "1_1") (pintype "passive"))
      (node (ref "R2") (pin "2") (pinfunction "2_2") (pintype "passive"))
      (node (ref "R3") (pin "2") (pinfunction "2_2") (pintype "passive"))
      (node (ref "R8") (pin "2") (pinfunction "2_2") (pintype "passive"))
      (node (ref "U1") (pin "5") (pinfunction "REF_5") (pintype "output"))
    )
  )
)
